# I2CPCB.net
KiCad netlist of a schematic drawn in EAGLE
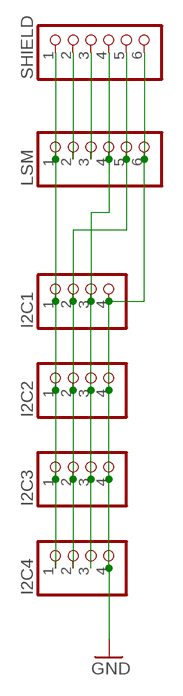
[diagram p0: schematic, sheet 1]

(export (version "E")
  (design (tool "Eeschema 10.0.6"))
  (components
    (comp (ref "I2C1")
      (value "PINHD-1X4")
      (footprint "eagle-import:1X04")
      (libsource (lib "eagle-import") (part "PINHD-1X4"))
    )
    (comp (ref "I2C2")
      (value "PINHD-1X4")
      (footprint "eagle-import:1X04")
      (libsource (lib "eagle-import") (part "PINHD-1X4"))
    )
    (comp (ref "I2C3")
      (value "PINHD-1X4")
      (footprint "eagle-import:1X04")
      (libsource (lib "eagle-import") (part "PINHD-1X4"))
    )
    (comp (ref "I2C4")
      (value "PINHD-1X4")
      (footprint "eagle-import:1X04")
      (libsource (lib "eagle-import") (part "PINHD-1X4"))
    )
    (comp (ref "LSM")
      (value "PINHD-1X6")
      (footprint "eagle-import:1X06")
      (libsource (lib "eagle-import") (part "PINHD-1X6"))
    )
    (comp (ref "SHIELD")
      (value "PINHD-1X6")
      (footprint "eagle-import:1X06")
      (libsource (lib "eagle-import") (part "PINHD-1X6"))
    )
  )
  (nets
    (net (code "1") (name "GND") (class "Default")
      (node (ref "I2C1") (pin "4") (pinfunction "4_4") (pintype "passive"))
      (node (ref "I2C2") (pin "4") (pinfunction "4_4") (pintype "passive"))
      (node (ref "I2C3") (pin "4") (pinfunction "4_4") (pintype "passive"))
      (node (ref "I2C4") (pin "4") (pinfunction "4_4") (pintype "passive"))
      (node (ref "LSM") (pin "6") (pinfunction "6_6") (pintype "passive"))
      (node (ref "SHIELD") (pin "6") (pinfunction "6_6") (pintype "passive"))
    )
    (net (code "2") (name "Net-(I2C1-Pad1)") (class "Default")
      (node (ref "I2C1") (pin "1") (pinfunction "1_1") (pintype "passive"))
      (node (ref "I2C2") (pin "1") (pinfunction "1_1") (pintype "passive"))
      (node (ref "I2C3") (pin "1") (pinfunction "1_1") (pintype "passive"))
      (node (ref "I2C4") (pin "1") (pinfunction "1_1") (pintype "passive"))
      (node (ref "LSM") (pin "1") (pinfunction "1_1") (pintype "passive"))
      (node (ref "SHIELD") (pin "1") (pinfunction "1_1") (pintype "passive"))
    )
    (net (code "3") (name "Net-(I2C1-Pad2)") (class "Default")
      (node (ref "I2C1") (pin "2") (pinfunction "2_2") (pintype "passive"))
      (node (ref "I2C2") (pin "2") (pinfunction "2_2") (pintype "passive"))
      (node (ref "I2C3") (pin "2") (pinfunction "2_2") (pintype "passive"))
      (node (ref "I2C4") (pin "2") (pinfunction "2_2") (pintype "passive"))
      (node (ref "LSM") (pin "5") (pinfunction "5_5") (pintype "passive"))
      (node (ref "SHIELD") (pin "5") (pinfunction "5_5") (pintype "passive"))
    )
    (net (code "4") (name "Net-(I2C1-Pad3)") (class "Default")
      (node (ref "I2C1") (pin "3") (pinfunction "3_3") (pintype "passive"))
      (node (ref "I2C2") (pin "3") (pinfunction "3_3") (pintype "passive"))
      (node (ref "I2C3") (pin "3") (pinfunction "3_3") (pintype "passive"))
      (node (ref "I2C4") (pin "3") (pinfunction "3_3") (pintype "passive"))
      (node (ref "LSM") (pin "4") (pinfunction "4_4") (pintype "passive"))
      (node (ref "SHIELD") (pin "4") (pinfunction "4_4") (pintype "passive"))
    )
    (net (code "5") (name "Net-(LSM-Pad2)") (class "Default")
      (node (ref "LSM") (pin "2") (pinfunction "2_2") (pintype "passive"))
      (node (ref "SHIELD") (pin "2") (pinfunction "2_2") (pintype "passive"))
    )
    (net (code "6") (name "Net-(LSM-Pad3)") (class "Default")
      (node (ref "LSM") (pin "3") (pinfunction "3_3") (pintype "passive"))
      (node (ref "SHIELD") (pin "3") (pinfunction "3_3") (pintype "passive"))
    )
  )
)
